# driver.net
KiCad netlist of a schematic drawn in EAGLE
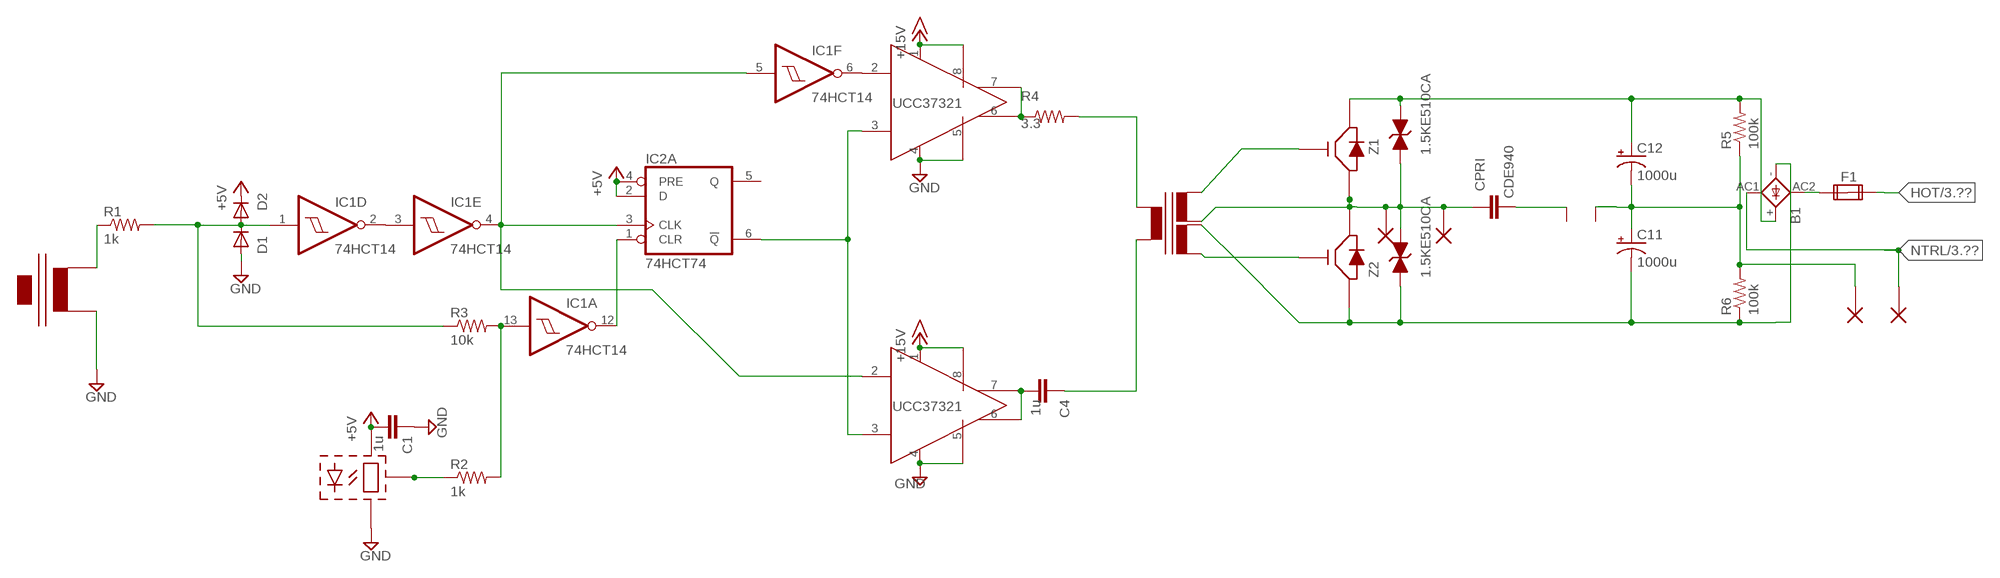
[diagram p0: schematic, sheet 1]
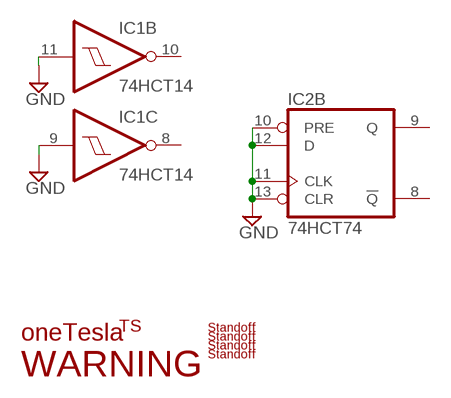
[diagram p1: schematic, sheet 2]
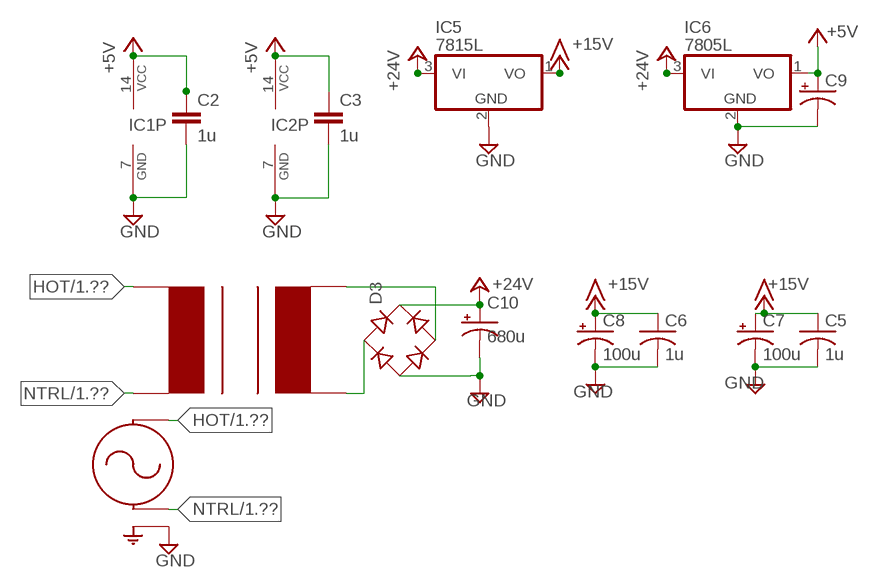
[diagram p2: schematic, sheet 3]

(export (version "E")
  (design (tool "Eeschema 10.0.6"))
  (components
    (comp (ref "IC1")
      (value "74HCT14")
      (footprint "eagle-import:DIL14")
      (libsource (lib "eagle-import") (part "7414NLS"))
    )
    (comp (ref "IC2")
      (value "74HCT74")
      (footprint "eagle-import:DIL14")
      (libsource (lib "eagle-import") (part "7474NLS"))
    )
    (comp (ref "U$1")
      (value "LOGO")
      (footprint "eagle-import:LOGO")
      (libsource (lib "eagle-import") (part "LOGO"))
    )
    (comp (ref "U$3")
      (value "WARNING")
      (footprint "eagle-import:WARNING")
      (libsource (lib "eagle-import") (part "WARNING"))
    )
    (comp (ref "U$4")
      (value "TS-LOGO")
      (footprint "eagle-import:TSLOGO")
      (libsource (lib "eagle-import") (part "TS-LOGO"))
    )
    (comp (ref "U$12")
      (value "STANDOFF-QTR")
      (footprint "eagle-import:STANDOFF")
      (libsource (lib "eagle-import") (part "STANDOFF-QTR"))
    )
    (comp (ref "U$13")
      (value "STANDOFF-QTR")
      (footprint "eagle-import:STANDOFF")
      (libsource (lib "eagle-import") (part "STANDOFF-QTR"))
    )
    (comp (ref "U$14")
      (value "STANDOFF-QTR")
      (footprint "eagle-import:STANDOFF")
      (libsource (lib "eagle-import") (part "STANDOFF-QTR"))
    )
    (comp (ref "U$15")
      (value "STANDOFF-QTR")
      (footprint "eagle-import:STANDOFF")
      (libsource (lib "eagle-import") (part "STANDOFF-QTR"))
    )
    (comp (ref "B1")
      (value "GBU4")
      (footprint "eagle-import:GBU4S")
      (libsource (lib "eagle-import") (part "GBU4"))
    )
    (comp (ref "C1")
      (value "1u")
      (footprint "eagle-import:C050-024X044@1")
      (libsource (lib "eagle-import") (part "C-EU050-024X044"))
    )
    (comp (ref "C4")
      (value "1u")
      (footprint "eagle-import:C050-024X044@1")
      (libsource (lib "eagle-import") (part "C-EU050-024X044"))
    )
    (comp (ref "C11")
      (value "1000u")
      (footprint "eagle-import:EB25D")
      (libsource (lib "eagle-import") (part "CPOL-USE10-25"))
    )
    (comp (ref "C12")
      (value "1000u")
      (footprint "eagle-import:EB25D")
      (libsource (lib "eagle-import") (part "CPOL-USE10-25"))
    )
    (comp (ref "CPRI")
      (value "CDE940")
      (footprint "eagle-import:CDE940")
      (libsource (lib "eagle-import") (part "CDE940"))
    )
    (comp (ref "D1")
      (value "1N4148DO35-7")
      (footprint "eagle-import:DO35-7")
      (libsource (lib "eagle-import") (part "1N4148DO35-7"))
    )
    (comp (ref "D2")
      (value "1N4148DO35-7")
      (footprint "eagle-import:DO35-7")
      (libsource (lib "eagle-import") (part "1N4148DO35-7"))
    )
    (comp (ref "F1")
      (value "FUSE2P")
      (footprint "eagle-import:FUSE1")
      (libsource (lib "eagle-import") (part "FUSE2P"))
    )
    (comp (ref "IC3")
      (value "UCC37321DIL8")
      (footprint "eagle-import:DIL08")
      (libsource (lib "eagle-import") (part "UCC37321DIL8"))
    )
    (comp (ref "IC4")
      (value "UCC37321DIL8")
      (footprint "eagle-import:DIL08")
      (libsource (lib "eagle-import") (part "UCC37321DIL8"))
    )
    (comp (ref "P1")
      (value "12AWG_PAD")
      (footprint "eagle-import:12AWG_PAD")
      (libsource (lib "eagle-import") (part "12AWG_PAD"))
    )
    (comp (ref "P2")
      (value "12AWG_PAD")
      (footprint "eagle-import:12AWG_PAD")
      (libsource (lib "eagle-import") (part "12AWG_PAD"))
    )
    (comp (ref "P3")
      (value "12AWG_PAD")
      (footprint "eagle-import:12AWG_PAD")
      (libsource (lib "eagle-import") (part "12AWG_PAD"))
    )
    (comp (ref "P4")
      (value "12AWG_PAD")
      (footprint "eagle-import:12AWG_PAD")
      (libsource (lib "eagle-import") (part "12AWG_PAD"))
    )
    (comp (ref "R1")
      (value "1k")
      (footprint "eagle-import:0922_22")
      (libsource (lib "eagle-import") (part "RES_5W"))
    )
    (comp (ref "R2")
      (value "1k")
      (footprint "eagle-import:0204_7")
      (libsource (lib "eagle-import") (part "R-US_0204/7"))
    )
    (comp (ref "R3")
      (value "10k")
      (footprint "eagle-import:0204_7")
      (libsource (lib "eagle-import") (part "R-US_0204/7"))
    )
    (comp (ref "R4")
      (value "3.3")
      (footprint "eagle-import:0204_7")
      (libsource (lib "eagle-import") (part "R-US_0204/7"))
    )
    (comp (ref "R5")
      (value "100k")
      (footprint "eagle-import:0309_10")
      (libsource (lib "eagle-import") (part "R-US_0309/10"))
    )
    (comp (ref "R6")
      (value "100k")
      (footprint "eagle-import:0309_10")
      (libsource (lib "eagle-import") (part "R-US_0309/10"))
    )
    (comp (ref "T1")
      (value "P0584")
      (footprint "eagle-import:P0584")
      (libsource (lib "eagle-import") (part "P0584"))
    )
    (comp (ref "U$2")
      (value "TRIAD_CT")
      (footprint "eagle-import:CT2")
      (libsource (lib "eagle-import") (part "TRIAD_CT"))
    )
    (comp (ref "U$5")
      (value "2STANDOFFS")
      (footprint "eagle-import:2STANDOFFS")
      (libsource (lib "eagle-import") (part "2STANDOFFS"))
    )
    (comp (ref "U$6")
      (value "IF-D95")
      (footprint "eagle-import:IFD95")
      (libsource (lib "eagle-import") (part "IF-D95"))
    )
    (comp (ref "U$7")
      (value "FGA60N65SMD")
      (footprint "eagle-import:TO247H")
      (libsource (lib "eagle-import") (part "FGA60N65SMD"))
    )
    (comp (ref "U$8")
      (value "FGA60N65SMD")
      (footprint "eagle-import:TO247H")
      (libsource (lib "eagle-import") (part "FGA60N65SMD"))
    )
    (comp (ref "Z1")
      (value "1.5KE510CA")
      (footprint "eagle-import:DO201")
      (libsource (lib "eagle-import") (part "1.5KE510CA"))
    )
    (comp (ref "Z2")
      (value "1.5KE510CA")
      (footprint "eagle-import:DO201")
      (libsource (lib "eagle-import") (part "1.5KE510CA"))
    )
    (comp (ref "C2")
      (value "1u")
      (footprint "eagle-import:C050-024X044@1")
      (libsource (lib "eagle-import") (part "C-EU050-024X044"))
    )
    (comp (ref "C3")
      (value "1u")
      (footprint "eagle-import:C050-024X044@1")
      (libsource (lib "eagle-import") (part "C-EU050-024X044"))
    )
    (comp (ref "C5")
      (value "1u")
      (footprint "eagle-import:C050-024X044")
      (libsource (lib "eagle-import") (part "C-US050-024X044"))
    )
    (comp (ref "C6")
      (value "1u")
      (footprint "eagle-import:C050-024X044")
      (libsource (lib "eagle-import") (part "C-US050-024X044"))
    )
    (comp (ref "C7")
      (value "100u")
      (footprint "eagle-import:E2,5-5")
      (libsource (lib "eagle-import") (part "CPOL-USE2.5-5"))
    )
    (comp (ref "C8")
      (value "100u")
      (footprint "eagle-import:E2,5-5")
      (libsource (lib "eagle-import") (part "CPOL-USE2.5-5"))
    )
    (comp (ref "C9")
      (value "CPOL-USE2.5-5")
      (footprint "eagle-import:E2,5-5")
      (libsource (lib "eagle-import") (part "CPOL-USE2.5-5"))
    )
    (comp (ref "C10")
      (value "680u")
      (footprint "eagle-import:E3,5-8")
      (libsource (lib "eagle-import") (part "CPOL-USE3.5-8"))
    )
    (comp (ref "D3")
      (value "B-DIL")
      (footprint "eagle-import:B-DIL")
      (libsource (lib "eagle-import") (part "B-DIL"))
    )
    (comp (ref "IC5")
      (value "7815L")
      (footprint "eagle-import:TO92")
      (libsource (lib "eagle-import") (part "78L15"))
    )
    (comp (ref "IC6")
      (value "7805L")
      (footprint "eagle-import:TO92")
      (libsource (lib "eagle-import") (part "78L05"))
    )
    (comp (ref "U$9")
      (value "EI30")
      (footprint "eagle-import:EL30")
      (libsource (lib "eagle-import") (part "EL30"))
    )
    (comp (ref "U$10")
      (value "IEC320/C6")
      (footprint "eagle-import:IEC320_C6")
      (libsource (lib "eagle-import") (part "IEC320/C6"))
    )
  )
  (nets
    (net (code "1") (name "+5V") (class "Default")
      (node (ref "C1") (pin "2") (pinfunction "2_2") (pintype "passive"))
      (node (ref "C2") (pin "1") (pinfunction "1_1") (pintype "passive"))
      (node (ref "C3") (pin "1") (pinfunction "1_1") (pintype "passive"))
      (node (ref "C9") (pin "+") (pinfunction "+_+") (pintype "passive"))
      (node (ref "D2") (pin "C") (pinfunction "C_C") (pintype "passive"))
      (node (ref "IC1") (pin "14") (pinfunction "VCC_14") (pintype "power_in"))
      (node (ref "IC2") (pin "14") (pinfunction "VCC_14") (pintype "power_in"))
      (node (ref "IC2") (pin "2") (pinfunction "D_2") (pintype "input"))
      (node (ref "IC2") (pin "4") (pinfunction "PRE_4") (pintype "input"))
      (node (ref "IC6") (pin "1") (pinfunction "VO_1") (pintype "passive"))
      (node (ref "U$6") (pin "V+") (pinfunction "VCC_V+") (pintype "bidirectional"))
    )
    (net (code "2") (name "+15V") (class "Default")
      (node (ref "C5") (pin "1") (pinfunction "1_1") (pintype "passive"))
      (node (ref "C6") (pin "1") (pinfunction "1_1") (pintype "passive"))
      (node (ref "C7") (pin "+") (pinfunction "+_+") (pintype "passive"))
      (node (ref "C8") (pin "+") (pinfunction "+_+") (pintype "passive"))
      (node (ref "IC3") (pin "1") (pinfunction "1_VDD_1") (pintype "power_in"))
      (node (ref "IC3") (pin "8") (pinfunction "8_VDD_8") (pintype "power_in"))
      (node (ref "IC4") (pin "1") (pinfunction "1_VDD_1") (pintype "power_in"))
      (node (ref "IC4") (pin "8") (pinfunction "8_VDD_8") (pintype "power_in"))
      (node (ref "IC5") (pin "1") (pinfunction "VO_1") (pintype "passive"))
    )
    (net (code "3") (name "+24V") (class "Default")
      (node (ref "C10") (pin "+") (pinfunction "+_+") (pintype "passive"))
      (node (ref "D3") (pin "+") (pinfunction "+_+") (pintype "passive"))
      (node (ref "IC5") (pin "3") (pinfunction "VI_3") (pintype "input"))
      (node (ref "IC6") (pin "3") (pinfunction "VI_3") (pintype "input"))
    )
    (net (code "4") (name "GND") (class "Default")
      (node (ref "C1") (pin "1") (pinfunction "1_1") (pintype "passive"))
      (node (ref "C10") (pin "-") (pinfunction "-_-") (pintype "passive"))
      (node (ref "C2") (pin "2") (pinfunction "2_2") (pintype "passive"))
      (node (ref "C3") (pin "2") (pinfunction "2_2") (pintype "passive"))
      (node (ref "C5") (pin "2") (pinfunction "2_2") (pintype "passive"))
      (node (ref "C6") (pin "2") (pinfunction "2_2") (pintype "passive"))
      (node (ref "C7") (pin "-") (pinfunction "-_-") (pintype "passive"))
      (node (ref "C8") (pin "-") (pinfunction "-_-") (pintype "passive"))
      (node (ref "C9") (pin "-") (pinfunction "-_-") (pintype "passive"))
      (node (ref "D1") (pin "A") (pinfunction "A_A") (pintype "passive"))
      (node (ref "D3") (pin "-") (pinfunction "-_-") (pintype "passive"))
      (node (ref "IC1") (pin "11") (pinfunction "I_11") (pintype "input"))
      (node (ref "IC1") (pin "7") (pinfunction "GND_7") (pintype "power_in"))
      (node (ref "IC1") (pin "9") (pinfunction "I_9") (pintype "input"))
      (node (ref "IC2") (pin "10") (pinfunction "PRE_10") (pintype "input"))
      (node (ref "IC2") (pin "11") (pinfunction "CLK_11") (pintype "input"))
      (node (ref "IC2") (pin "12") (pinfunction "D_12") (pintype "input"))
      (node (ref "IC2") (pin "13") (pinfunction "CLR_13") (pintype "input"))
      (node (ref "IC2") (pin "7") (pinfunction "GND_7") (pintype "power_in"))
      (node (ref "IC3") (pin "4") (pinfunction "4_AGND_4") (pintype "power_in"))
      (node (ref "IC3") (pin "5") (pinfunction "5_PGND_5") (pintype "power_in"))
      (node (ref "IC4") (pin "4") (pinfunction "4_AGND_4") (pintype "power_in"))
      (node (ref "IC4") (pin "5") (pinfunction "5_PGND_5") (pintype "power_in"))
      (node (ref "IC5") (pin "2") (pinfunction "GND_2") (pintype "passive"))
      (node (ref "IC6") (pin "2") (pinfunction "GND_2") (pintype "passive"))
      (node (ref "U$10") (pin "G") (pinfunction "G_G") (pintype "bidirectional"))
      (node (ref "U$2") (pin "P$2") (pinfunction "P$2_P$2") (pintype "output"))
      (node (ref "U$6") (pin "GND") (pinfunction "GND_GND") (pintype "bidirectional"))
    )
    (net (code "5") (name "HOT") (class "Default")
      (node (ref "F1") (pin "2A") (pinfunction "2A_2A") (pintype "passive"))
      (node (ref "U$10") (pin "H") (pinfunction "H_H") (pintype "bidirectional"))
      (node (ref "U$9") (pin "1") (pinfunction "P$1_1") (pintype "bidirectional"))
    )
    (net (code "6") (name "NTRL") (class "Default")
      (node (ref "B1") (pin "AC1") (pinfunction "AC2_AC1") (pintype "passive"))
      (node (ref "P4") (pin "P$1") (pinfunction "P$1_P$1") (pintype "bidirectional"))
      (node (ref "U$10") (pin "N") (pinfunction "N_N") (pintype "bidirectional"))
      (node (ref "U$9") (pin "5") (pinfunction "P$2_5") (pintype "bidirectional"))
    )
    (net (code "7") (name "Net-(B1-AC1)") (class "Default")
      (node (ref "B1") (pin "AC2") (pinfunction "AC1_AC2") (pintype "passive"))
      (node (ref "F1") (pin "1A") (pinfunction "1A_1A") (pintype "passive"))
    )
    (net (code "8") (name "Net-(B1-Pad+)") (class "Default")
      (node (ref "B1") (pin "+") (pinfunction "+_+") (pintype "passive"))
      (node (ref "C12") (pin "+") (pinfunction "+_+") (pintype "passive"))
      (node (ref "R5") (pin "2") (pinfunction "2_2") (pintype "passive"))
      (node (ref "U$7") (pin "C") (pinfunction "C_C") (pintype "bidirectional"))
      (node (ref "Z1") (pin "C") (pinfunction "C_C") (pintype "passive"))
    )
    (net (code "9") (name "Net-(C11-Pad+)") (class "Default")
      (node (ref "C11") (pin "+") (pinfunction "+_+") (pintype "passive"))
      (node (ref "C12") (pin "-") (pinfunction "-_-") (pintype "passive"))
      (node (ref "P3") (pin "P$1") (pinfunction "P$1_P$1") (pintype "bidirectional"))
      (node (ref "R5") (pin "1") (pinfunction "1_1") (pintype "passive"))
      (node (ref "R6") (pin "2") (pinfunction "2_2") (pintype "passive"))
      (node (ref "U$5") (pin "P$1") (pinfunction "P$1_P$1") (pintype "bidirectional"))
    )
    (net (code "10") (name "Net-(CPRI-1)") (class "Default")
      (node (ref "CPRI") (pin "P$1") (pinfunction "1_P$1") (pintype "passive"))
      (node (ref "P1") (pin "P$1") (pinfunction "P$1_P$1") (pintype "bidirectional"))
      (node (ref "P2") (pin "P$1") (pinfunction "P$1_P$1") (pintype "bidirectional"))
      (node (ref "T1") (pin "4") (pinfunction "SEC1B_4") (pintype "output"))
      (node (ref "U$7") (pin "E") (pinfunction "E_E") (pintype "bidirectional"))
      (node (ref "U$8") (pin "C") (pinfunction "C_C") (pintype "bidirectional"))
      (node (ref "Z1") (pin "A") (pinfunction "A_A") (pintype "passive"))
      (node (ref "Z2") (pin "C") (pinfunction "C_C") (pintype "passive"))
    )
    (net (code "11") (name "Net-(CPRI-2)") (class "Default")
      (node (ref "CPRI") (pin "P$2") (pinfunction "2_P$2") (pintype "passive"))
      (node (ref "U$5") (pin "P$2") (pinfunction "P$2_P$2") (pintype "bidirectional"))
    )
    (net (code "12") (name "Net-(IC1A-I)") (class "Default")
      (node (ref "IC1") (pin "13") (pinfunction "I_13") (pintype "input"))
      (node (ref "R2") (pin "2") (pinfunction "2_2") (pintype "passive"))
      (node (ref "R3") (pin "2") (pinfunction "2_2") (pintype "passive"))
    )
    (net (code "13") (name "Net-(IC1A-O)") (class "Default")
      (node (ref "IC1") (pin "12") (pinfunction "O_12") (pintype "output"))
      (node (ref "IC2") (pin "1") (pinfunction "CLR_1") (pintype "input"))
    )
    (net (code "14") (name "Net-(IC1D-I)") (class "Default")
      (node (ref "D1") (pin "C") (pinfunction "C_C") (pintype "passive"))
      (node (ref "D2") (pin "A") (pinfunction "A_A") (pintype "passive"))
      (node (ref "IC1") (pin "1") (pinfunction "I_1") (pintype "input"))
      (node (ref "R1") (pin "2") (pinfunction "2_2") (pintype "passive"))
      (node (ref "R3") (pin "1") (pinfunction "1_1") (pintype "passive"))
    )
    (net (code "15") (name "Net-(IC1D-O)") (class "Default")
      (node (ref "IC1") (pin "2") (pinfunction "O_2") (pintype "output"))
      (node (ref "IC1") (pin "3") (pinfunction "I_3") (pintype "input"))
    )
    (net (code "16") (name "Net-(IC1E-O)") (class "Default")
      (node (ref "IC1") (pin "4") (pinfunction "O_4") (pintype "output"))
      (node (ref "IC1") (pin "5") (pinfunction "I_5") (pintype "input"))
      (node (ref "IC2") (pin "3") (pinfunction "CLK_3") (pintype "input"))
      (node (ref "IC4") (pin "2") (pinfunction "2_IN_2") (pintype "input"))
    )
    (net (code "17") (name "Net-(IC1F-O)") (class "Default")
      (node (ref "IC1") (pin "6") (pinfunction "O_6") (pintype "output"))
      (node (ref "IC3") (pin "2") (pinfunction "2_IN_2") (pintype "input"))
    )
    (net (code "18") (name "Net-(IC2A-~{Q})") (class "Default")
      (node (ref "IC2") (pin "6") (pinfunction "~{Q}_6") (pintype "output"))
      (node (ref "IC3") (pin "3") (pinfunction "3_ENBL_3") (pintype "input"))
      (node (ref "IC4") (pin "3") (pinfunction "3_ENBL_3") (pintype "input"))
    )
    (net (code "19") (name "Net-(IC3-6_OUT)") (class "Default")
      (node (ref "IC3") (pin "6") (pinfunction "6_OUT_6") (pintype "output"))
      (node (ref "IC3") (pin "7") (pinfunction "7_OUT_7") (pintype "output"))
      (node (ref "R4") (pin "1") (pinfunction "1_1") (pintype "passive"))
    )
    (net (code "20") (name "Net-(IC4-6_OUT)") (class "Default")
      (node (ref "C4") (pin "2") (pinfunction "2_2") (pintype "passive"))
      (node (ref "IC4") (pin "6") (pinfunction "6_OUT_6") (pintype "output"))
      (node (ref "IC4") (pin "7") (pinfunction "7_OUT_7") (pintype "output"))
    )
    (net (code "21") (name "Net-(R1-Pad1)") (class "Default")
      (node (ref "R1") (pin "1") (pinfunction "1_1") (pintype "passive"))
      (node (ref "U$2") (pin "P$1") (pinfunction "P$1_P$1") (pintype "output"))
    )
    (net (code "22") (name "Net-(R2-Pad1)") (class "Default")
      (node (ref "R2") (pin "1") (pinfunction "1_1") (pintype "passive"))
      (node (ref "U$6") (pin "OUT") (pinfunction "OUT_OUT") (pintype "bidirectional"))
    )
    (net (code "23") (name "Net-(T1-PRIA)") (class "Default")
      (node (ref "R4") (pin "2") (pinfunction "2_2") (pintype "passive"))
      (node (ref "T1") (pin "1") (pinfunction "PRIA_1") (pintype "input"))
    )
    (net (code "24") (name "Net-(T1-PRIB)") (class "Default")
      (node (ref "C4") (pin "1") (pinfunction "1_1") (pintype "passive"))
      (node (ref "T1") (pin "10") (pinfunction "PRIB_10") (pintype "input"))
    )
    (net (code "25") (name "Net-(T1-SEC1A)") (class "Default")
      (node (ref "T1") (pin "3") (pinfunction "SEC1A_3") (pintype "output"))
      (node (ref "U$7") (pin "G") (pinfunction "G_G") (pintype "bidirectional"))
    )
    (net (code "26") (name "Net-(T1-SEC2A)") (class "Default")
      (node (ref "B1") (pin "-") (pinfunction "-_-") (pintype "passive"))
      (node (ref "C11") (pin "-") (pinfunction "-_-") (pintype "passive"))
      (node (ref "R6") (pin "1") (pinfunction "1_1") (pintype "passive"))
      (node (ref "T1") (pin "8") (pinfunction "SEC2A_8") (pintype "output"))
      (node (ref "U$8") (pin "E") (pinfunction "E_E") (pintype "bidirectional"))
      (node (ref "Z2") (pin "A") (pinfunction "A_A") (pintype "passive"))
    )
    (net (code "27") (name "Net-(T1-SEC2B)") (class "Default")
      (node (ref "T1") (pin "7") (pinfunction "SEC2B_7") (pintype "output"))
      (node (ref "U$8") (pin "G") (pinfunction "G_G") (pintype "bidirectional"))
    )
    (net (code "28") (name "Net-(U$9-P$3)") (class "Default")
      (node (ref "D3") (pin "AC2") (pinfunction "AC2_AC2") (pintype "passive"))
      (node (ref "U$9") (pin "7") (pinfunction "P$3_7") (pintype "bidirectional"))
    )
    (net (code "29") (name "Net-(U$9-P$4)") (class "Default")
      (node (ref "D3") (pin "AC1") (pinfunction "AC1_AC1") (pintype "passive"))
      (node (ref "U$9") (pin "9") (pinfunction "P$4_9") (pintype "bidirectional"))
    )
    (net (code "30") (name "unconnected-(F1-Pad1B)") (class "Default")
      (node (ref "F1") (pin "1B") (pinfunction "1B_1B") (pintype "passive"))
    )
    (net (code "31") (name "unconnected-(F1-Pad2B)") (class "Default")
      (node (ref "F1") (pin "2B") (pinfunction "2B_2B") (pintype "passive"))
    )
    (net (code "32") (name "unconnected-(IC1B-O-Pad10)") (class "Default")
      (node (ref "IC1") (pin "10") (pinfunction "O_10") (pintype "output"))
    )
    (net (code "33") (name "unconnected-(IC1C-O-Pad8)") (class "Default")
      (node (ref "IC1") (pin "8") (pinfunction "O_8") (pintype "output"))
    )
    (net (code "34") (name "unconnected-(IC2A-Q-Pad5)") (class "Default")
      (node (ref "IC2") (pin "5") (pinfunction "Q_5") (pintype "output"))
    )
    (net (code "35") (name "unconnected-(IC2B-Q-Pad9)") (class "Default")
      (node (ref "IC2") (pin "9") (pinfunction "Q_9") (pintype "output"))
    )
    (net (code "36") (name "unconnected-(IC2B-~{Q}-Pad8)") (class "Default")
      (node (ref "IC2") (pin "8") (pinfunction "~{Q}_8") (pintype "output"))
    )
  )
)
